# gauges_ser.net
KiCad netlist of a schematic drawn in EAGLE
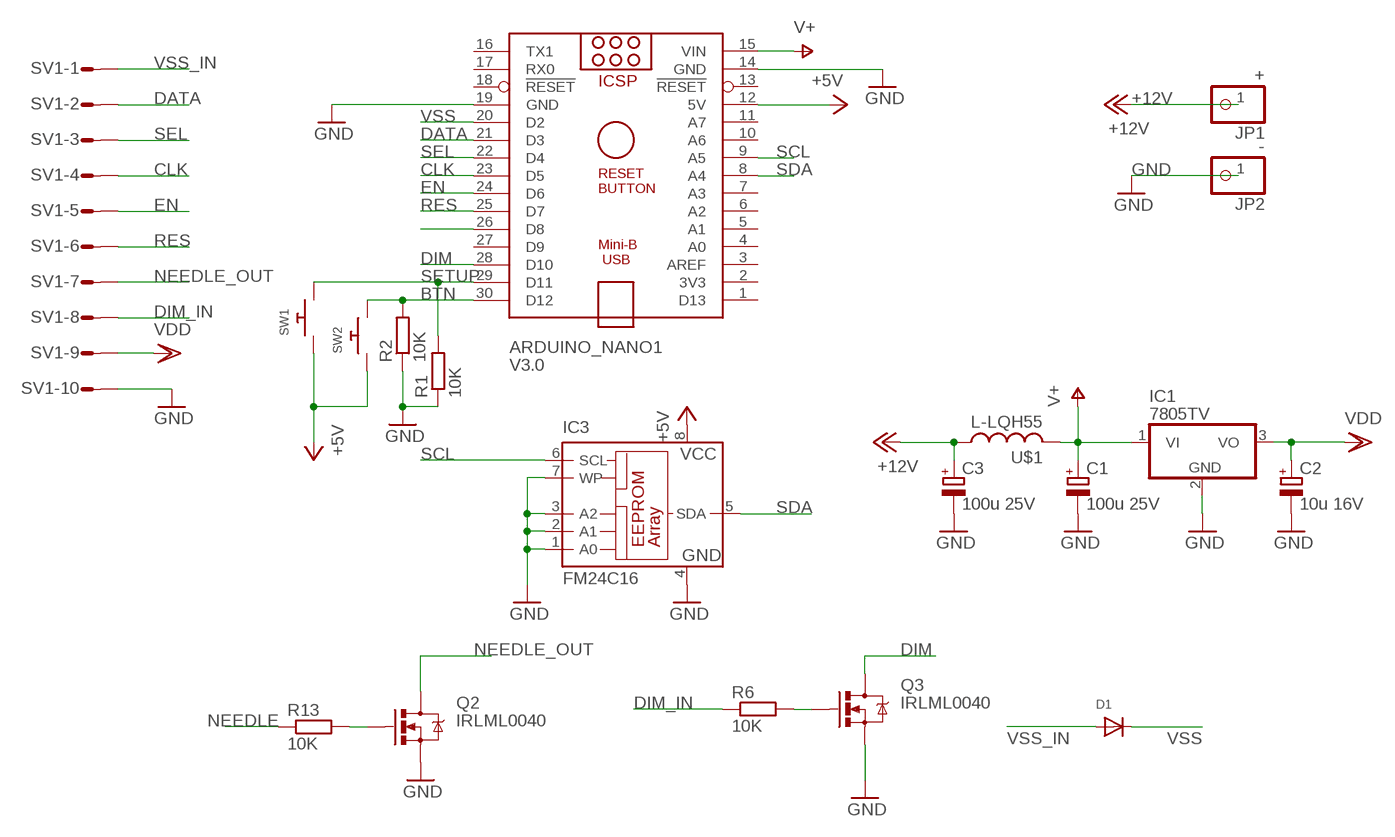
[diagram p0: schematic, sheet 1]

(export (version "E")
  (design (tool "Eeschema 10.0.6"))
  (components
    (comp (ref "ARDUINO_NANO1")
      (value "V3.0")
      (footprint "eagle-import:ARDUINO_NANO")
      (libsource (lib "eagle-import") (part "ARDUINO_NANO"))
    )
    (comp (ref "C1")
      (value "100u 25V")
      (footprint "eagle-import:SMC_D")
      (libsource (lib "eagle-import") (part "CPOL-EUSMCD"))
    )
    (comp (ref "C2")
      (value "10u 16V")
      (footprint "eagle-import:SMC_B")
      (libsource (lib "eagle-import") (part "CPOL-EUSMCB"))
    )
    (comp (ref "C3")
      (value "100u 25V")
      (footprint "eagle-import:SMC_D")
      (libsource (lib "eagle-import") (part "CPOL-EUSMCD"))
    )
    (comp (ref "D1")
      (value "DIODESOD-123")
      (footprint "eagle-import:SOD-123")
      (libsource (lib "eagle-import") (part "DIODESOD-123"))
    )
    (comp (ref "IC1")
      (value "7805TV")
      (footprint "eagle-import:TO220V")
      (libsource (lib "eagle-import") (part "78TV05"))
    )
    (comp (ref "IC3")
      (value "FM24C16")
      (footprint "eagle-import:SO-08M")
      (fields (field (name "MF") "MICROCHIP") (field (name "MPN") "24LC64T-I/SN"))
      (libsource (lib "eagle-import") (part "24SMLC64"))
    )
    (comp (ref "JP1")
      (value "+")
      (footprint "eagle-import:1X01")
      (libsource (lib "eagle-import") (part "PINHD-1X1"))
    )
    (comp (ref "JP2")
      (value "-")
      (footprint "eagle-import:1X01")
      (libsource (lib "eagle-import") (part "PINHD-1X1"))
    )
    (comp (ref "Q2")
      (value "IRLML0040")
      (footprint "eagle-import:SOT23-3")
      (libsource (lib "eagle-import") (part "MOSFET-NCHANNELAO3404A"))
    )
    (comp (ref "Q3")
      (value "IRLML0040")
      (footprint "eagle-import:SOT23-3")
      (libsource (lib "eagle-import") (part "MOSFET-NCHANNELAO3404A"))
    )
    (comp (ref "R1")
      (value "10K")
      (footprint "eagle-import:R0805")
      (libsource (lib "eagle-import") (part "R-EU_R0805"))
    )
    (comp (ref "R2")
      (value "10K")
      (footprint "eagle-import:R0805")
      (libsource (lib "eagle-import") (part "R-EU_R0805"))
    )
    (comp (ref "R6")
      (value "10K")
      (footprint "eagle-import:R0805")
      (libsource (lib "eagle-import") (part "R-EU_R0805"))
    )
    (comp (ref "R13")
      (value "10K")
      (footprint "eagle-import:R0805")
      (libsource (lib "eagle-import") (part "R-EU_R0805"))
    )
    (comp (ref "SV1")
      (value "L10P")
      (footprint "eagle-import:L10P")
      (libsource (lib "eagle-import") (part "L10P"))
    )
    (comp (ref "SW1")
      (value "SWITCH_PUSHBUTTONEVQ-PE")
      (footprint "eagle-import:TACT_PANA-EVQ")
      (libsource (lib "eagle-import") (part "SWITCH_PUSHBUTTONEVQ-PE"))
    )
    (comp (ref "SW2")
      (value "SWITCH_PUSHBUTTONEVQ-PE")
      (footprint "eagle-import:TACT_PANA-EVQ")
      (libsource (lib "eagle-import") (part "SWITCH_PUSHBUTTONEVQ-PE"))
    )
    (comp (ref "U$1")
      (value "L-LQH55")
      (footprint "eagle-import:LQH55")
      (libsource (lib "eagle-import") (part "L-LQH55"))
    )
  )
  (nets
    (net (code "1") (name "+5V") (class "Default")
      (node (ref "ARDUINO_NANO1") (pin "12") (pinfunction "5V_12") (pintype "power_in"))
      (node (ref "IC3") (pin "8") (pinfunction "VCC_8") (pintype "power_in"))
      (node (ref "SW1") (pin "P$1") (pinfunction "P$1_P$1") (pintype "passive"))
      (node (ref "SW2") (pin "P$1") (pinfunction "P$1_P$1") (pintype "passive"))
    )
    (net (code "2") (name "+12V") (class "Default")
      (node (ref "C3") (pin "+") (pinfunction "+_+") (pintype "passive"))
      (node (ref "JP1") (pin "1") (pinfunction "1_1") (pintype "passive"))
      (node (ref "U$1") (pin "1") (pinfunction "1_1") (pintype "passive"))
    )
    (net (code "3") (name "/BTN") (class "Default")
      (node (ref "ARDUINO_NANO1") (pin "30") (pinfunction "D12_30") (pintype "bidirectional"))
      (node (ref "R2") (pin "2") (pinfunction "2_2") (pintype "passive"))
      (node (ref "SW2") (pin "P$2") (pinfunction "P$2_P$2") (pintype "passive"))
    )
    (net (code "4") (name "/CLK") (class "Default")
      (node (ref "ARDUINO_NANO1") (pin "23") (pinfunction "D5_23") (pintype "bidirectional"))
      (node (ref "SV1") (pin "4") (pinfunction "S_4") (pintype "passive"))
    )
    (net (code "5") (name "/DATA") (class "Default")
      (node (ref "ARDUINO_NANO1") (pin "21") (pinfunction "D3_21") (pintype "bidirectional"))
      (node (ref "SV1") (pin "2") (pinfunction "S_2") (pintype "passive"))
    )
    (net (code "6") (name "/DIM") (class "Default")
      (node (ref "ARDUINO_NANO1") (pin "28") (pinfunction "D10_28") (pintype "bidirectional"))
      (node (ref "Q3") (pin "3") (pinfunction "D_3") (pintype "passive"))
    )
    (net (code "7") (name "/DIM_IN") (class "Default")
      (node (ref "R6") (pin "1") (pinfunction "1_1") (pintype "passive"))
      (node (ref "SV1") (pin "8") (pinfunction "S_8") (pintype "passive"))
    )
    (net (code "8") (name "/EN") (class "Default")
      (node (ref "ARDUINO_NANO1") (pin "24") (pinfunction "D6_24") (pintype "bidirectional"))
      (node (ref "SV1") (pin "5") (pinfunction "S_5") (pintype "passive"))
    )
    (net (code "9") (name "/NEEDLE") (class "Default")
      (node (ref "ARDUINO_NANO1") (pin "26") (pinfunction "D8_26") (pintype "bidirectional"))
      (node (ref "R13") (pin "1") (pinfunction "1_1") (pintype "passive"))
    )
    (net (code "10") (name "/NEEDLE_OUT") (class "Default")
      (node (ref "Q2") (pin "3") (pinfunction "D_3") (pintype "passive"))
      (node (ref "SV1") (pin "7") (pinfunction "S_7") (pintype "passive"))
    )
    (net (code "11") (name "/RES") (class "Default")
      (node (ref "ARDUINO_NANO1") (pin "25") (pinfunction "D7_25") (pintype "bidirectional"))
      (node (ref "SV1") (pin "6") (pinfunction "S_6") (pintype "passive"))
    )
    (net (code "12") (name "/SCL") (class "Default")
      (node (ref "ARDUINO_NANO1") (pin "9") (pinfunction "A5_9") (pintype "bidirectional"))
      (node (ref "IC3") (pin "6") (pinfunction "SCL_6") (pintype "input"))
    )
    (net (code "13") (name "/SDA") (class "Default")
      (node (ref "ARDUINO_NANO1") (pin "8") (pinfunction "A4_8") (pintype "bidirectional"))
      (node (ref "IC3") (pin "5") (pinfunction "SDA_5") (pintype "bidirectional"))
    )
    (net (code "14") (name "/SEL") (class "Default")
      (node (ref "ARDUINO_NANO1") (pin "22") (pinfunction "D4_22") (pintype "bidirectional"))
      (node (ref "SV1") (pin "3") (pinfunction "S_3") (pintype "passive"))
    )
    (net (code "15") (name "/SETUP") (class "Default")
      (node (ref "ARDUINO_NANO1") (pin "29") (pinfunction "D11_29") (pintype "bidirectional"))
      (node (ref "R1") (pin "2") (pinfunction "2_2") (pintype "passive"))
      (node (ref "SW1") (pin "P$2") (pinfunction "P$2_P$2") (pintype "passive"))
    )
    (net (code "16") (name "/VSS") (class "Default")
      (node (ref "ARDUINO_NANO1") (pin "20") (pinfunction "D2_20") (pintype "bidirectional"))
      (node (ref "D1") (pin "C") (pinfunction "C_C") (pintype "passive"))
    )
    (net (code "17") (name "/VSS_IN") (class "Default")
      (node (ref "D1") (pin "A") (pinfunction "A_A") (pintype "passive"))
      (node (ref "SV1") (pin "1") (pinfunction "S_1") (pintype "passive"))
    )
    (net (code "18") (name "GND") (class "Default")
      (node (ref "ARDUINO_NANO1") (pin "14") (pinfunction "GND_14") (pintype "power_in"))
      (node (ref "ARDUINO_NANO1") (pin "19") (pinfunction "GND_19") (pintype "power_in"))
      (node (ref "C1") (pin "-") (pinfunction "-_-") (pintype "passive"))
      (node (ref "C2") (pin "-") (pinfunction "-_-") (pintype "passive"))
      (node (ref "C3") (pin "-") (pinfunction "-_-") (pintype "passive"))
      (node (ref "IC1") (pin "2") (pinfunction "GND_2") (pintype "passive"))
      (node (ref "IC3") (pin "1") (pinfunction "A0_1") (pintype "input"))
      (node (ref "IC3") (pin "2") (pinfunction "A1_2") (pintype "input"))
      (node (ref "IC3") (pin "3") (pinfunction "A2_3") (pintype "input"))
      (node (ref "IC3") (pin "4") (pinfunction "GND_4") (pintype "power_in"))
      (node (ref "IC3") (pin "7") (pinfunction "WP_7") (pintype "input"))
      (node (ref "JP2") (pin "1") (pinfunction "1_1") (pintype "passive"))
      (node (ref "Q2") (pin "2") (pinfunction "S_2") (pintype "passive"))
      (node (ref "Q3") (pin "2") (pinfunction "S_2") (pintype "passive"))
      (node (ref "R1") (pin "1") (pinfunction "1_1") (pintype "passive"))
      (node (ref "R2") (pin "1") (pinfunction "1_1") (pintype "passive"))
      (node (ref "SV1") (pin "10") (pinfunction "S_10") (pintype "passive"))
    )
    (net (code "19") (name "Net-(Q2-G)") (class "Default")
      (node (ref "Q2") (pin "1") (pinfunction "G_1") (pintype "passive"))
      (node (ref "R13") (pin "2") (pinfunction "2_2") (pintype "passive"))
    )
    (net (code "20") (name "Net-(Q3-G)") (class "Default")
      (node (ref "Q3") (pin "1") (pinfunction "G_1") (pintype "passive"))
      (node (ref "R6") (pin "2") (pinfunction "2_2") (pintype "passive"))
    )
    (net (code "21") (name "V+") (class "Default")
      (node (ref "ARDUINO_NANO1") (pin "15") (pinfunction "VIN_15") (pintype "power_in"))
      (node (ref "C1") (pin "+") (pinfunction "+_+") (pintype "passive"))
      (node (ref "IC1") (pin "1") (pinfunction "VI_1") (pintype "input"))
      (node (ref "U$1") (pin "2") (pinfunction "2_2") (pintype "passive"))
    )
    (net (code "22") (name "VDD") (class "Default")
      (node (ref "C2") (pin "+") (pinfunction "+_+") (pintype "passive"))
      (node (ref "IC1") (pin "3") (pinfunction "VO_3") (pintype "passive"))
      (node (ref "SV1") (pin "9") (pinfunction "S_9") (pintype "passive"))
    )
    (net (code "23") (name "unconnected-(ARDUINO_NANO1-3V3-Pad2)") (class "Default")
      (node (ref "ARDUINO_NANO1") (pin "2") (pinfunction "3V3_2") (pintype "output"))
    )
    (net (code "24") (name "unconnected-(ARDUINO_NANO1-A0-Pad4)") (class "Default")
      (node (ref "ARDUINO_NANO1") (pin "4") (pinfunction "A0_4") (pintype "bidirectional"))
    )
    (net (code "25") (name "unconnected-(ARDUINO_NANO1-A1-Pad5)") (class "Default")
      (node (ref "ARDUINO_NANO1") (pin "5") (pinfunction "A1_5") (pintype "bidirectional"))
    )
    (net (code "26") (name "unconnected-(ARDUINO_NANO1-A2-Pad6)") (class "Default")
      (node (ref "ARDUINO_NANO1") (pin "6") (pinfunction "A2_6") (pintype "bidirectional"))
    )
    (net (code "27") (name "unconnected-(ARDUINO_NANO1-A3-Pad7)") (class "Default")
      (node (ref "ARDUINO_NANO1") (pin "7") (pinfunction "A3_7") (pintype "bidirectional"))
    )
    (net (code "28") (name "unconnected-(ARDUINO_NANO1-A6-Pad10)") (class "Default")
      (node (ref "ARDUINO_NANO1") (pin "10") (pinfunction "A6_10") (pintype "bidirectional"))
    )
    (net (code "29") (name "unconnected-(ARDUINO_NANO1-A7-Pad11)") (class "Default")
      (node (ref "ARDUINO_NANO1") (pin "11") (pinfunction "A7_11") (pintype "bidirectional"))
    )
    (net (code "30") (name "unconnected-(ARDUINO_NANO1-AREF-Pad3)") (class "Default")
      (node (ref "ARDUINO_NANO1") (pin "3") (pinfunction "AREF_3") (pintype "input"))
    )
    (net (code "31") (name "unconnected-(ARDUINO_NANO1-D9-Pad27)") (class "Default")
      (node (ref "ARDUINO_NANO1") (pin "27") (pinfunction "D9_27") (pintype "bidirectional"))
    )
    (net (code "32") (name "unconnected-(ARDUINO_NANO1-D13-Pad1)") (class "Default")
      (node (ref "ARDUINO_NANO1") (pin "1") (pinfunction "D13_1") (pintype "bidirectional"))
    )
    (net (code "33") (name "unconnected-(ARDUINO_NANO1-RX0-Pad17)") (class "Default")
      (node (ref "ARDUINO_NANO1") (pin "17") (pinfunction "RX0_17") (pintype "bidirectional"))
    )
    (net (code "34") (name "unconnected-(ARDUINO_NANO1-TX1-Pad16)") (class "Default")
      (node (ref "ARDUINO_NANO1") (pin "16") (pinfunction "TX1_16") (pintype "bidirectional"))
    )
    (net (code "35") (name "unconnected-(ARDUINO_NANO1-~{RESET}-Pad13)") (class "Default")
      (node (ref "ARDUINO_NANO1") (pin "13") (pinfunction "~{RESET}_13") (pintype "input"))
    )
    (net (code "36") (name "unconnected-(ARDUINO_NANO1-~{RESET}-Pad18)") (class "Default")
      (node (ref "ARDUINO_NANO1") (pin "18") (pinfunction "~{RESET}_18") (pintype "input"))
    )
  )
)
